# Clock_Distribution.net
KiCad netlist of a schematic drawn in Altium Designer
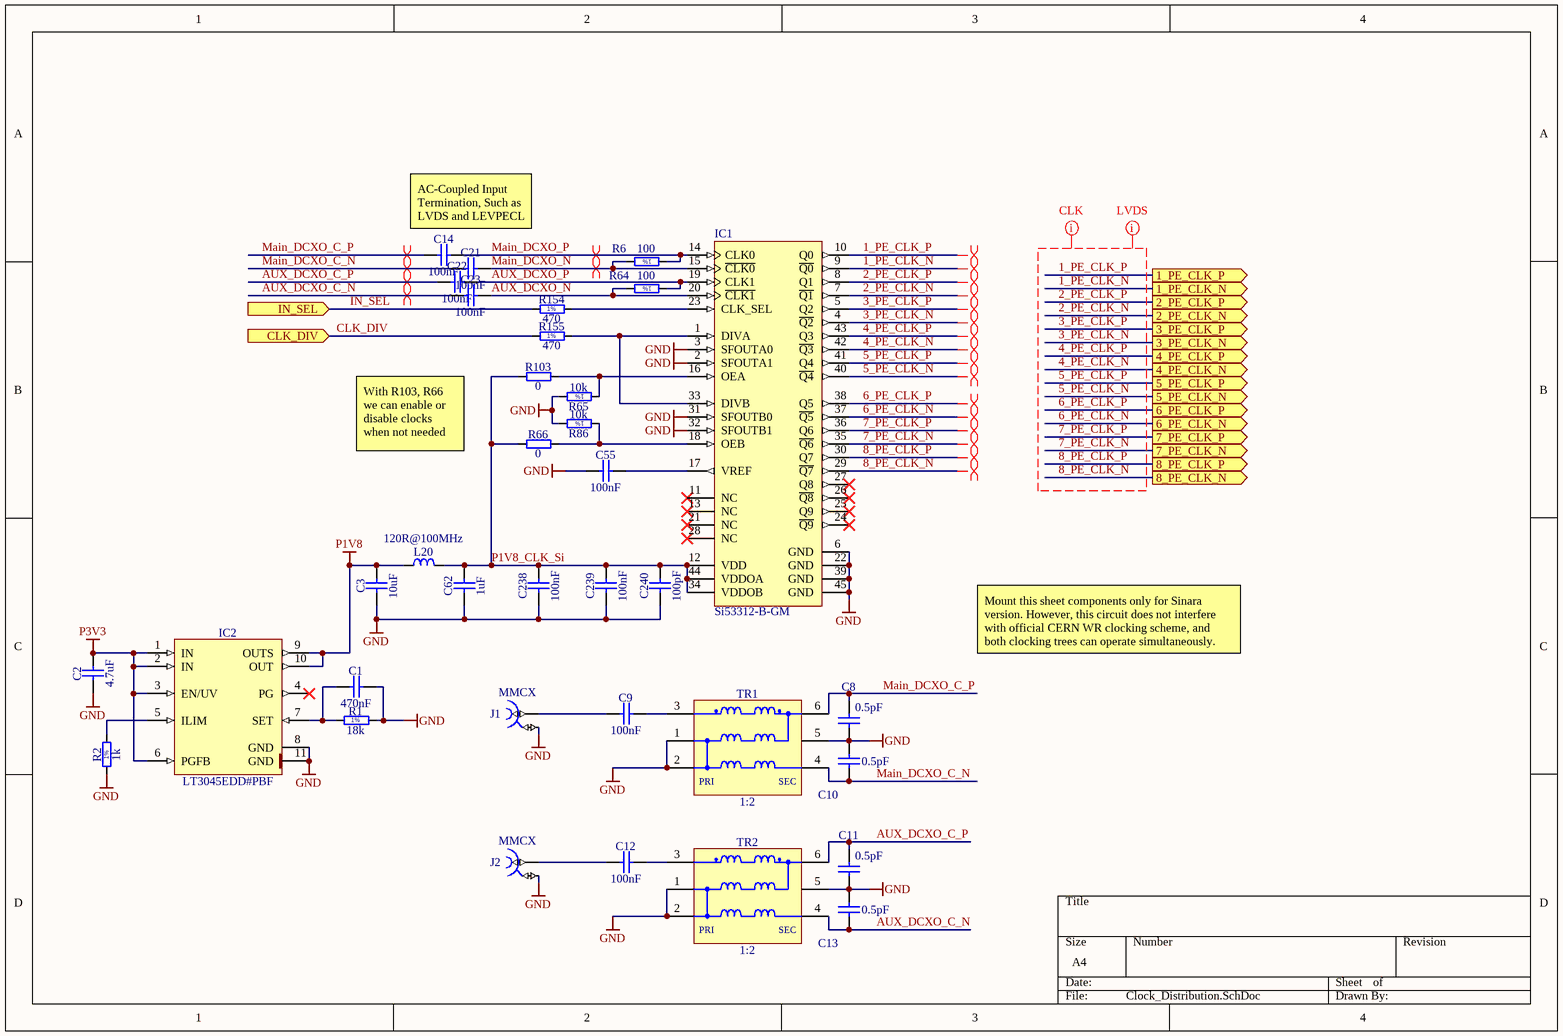
[diagram p0: Clock_Distribution.SchDoc]

(export (version "E")
  (design (tool "Eeschema 10.0.6"))
  (components
    (comp (ref "C1")
      (value "470nF")
      (footprint "CAPC1005X55N")
      (description "Non-polarised capacitor")
      (fields
        (field (name "PART NUMBER") "CC0402_470NF_16V_10%_X5R")
        (field (name "VOLTAGE") "16V")
        (field (name "AUTHOR") "CERN DEM JLC")
      )
      (libsource (lib "Capacitors") (part "Capacitor - non polarized"))
    )
    (comp (ref "C2")
      (value "4.7uF")
      (footprint "CAPC1709X95N")
      (description "Non-polarised capacitor")
      (fields
        (field (name "PART NUMBER") "CC0603_4.7UF_16V_10%_X5R")
        (field (name "VOLTAGE") "16V")
        (field (name "AUTHOR") "CERN DEM JLC")
      )
      (libsource (lib "Capacitors") (part "Capacitor - non polarized"))
    )
    (comp (ref "C3")
      (value "10uF")
      (footprint "CAPC1608X80N")
      (description "Non-polarised capacitor")
      (fields
        (field (name "PART NUMBER") "CC0603_10UF_10V_10%_X5R")
        (field (name "VOLTAGE") "10V")
        (field (name "AUTHOR") "CERN DEM JLC")
      )
      (libsource (lib "Capacitors") (part "Capacitor - non polarized"))
    )
    (comp (ref "C8")
      (value "0.5pF")
      (footprint "CAPC1005X50N")
      (description "Non-polarised capacitor")
      (fields
        (field (name "PART NUMBER") "CC0402_0.5PF_25V_0.05PF_AVX_04023J0R5ABSTR")
        (field (name "VOLTAGE") "25V")
        (field (name "AUTHOR") "CERN DEM JLC")
      )
      (libsource (lib "Capacitors") (part "Capacitor - non polarized"))
    )
    (comp (ref "C9")
      (value "100nF")
      (footprint "CAPC1005X55N")
      (description "Non-polarised capacitor")
      (fields
        (field (name "PART NUMBER") "CC0402_100NF_16V_10%_X5R")
        (field (name "VOLTAGE") "16V")
        (field (name "AUTHOR") "CERN DEM JLC")
      )
      (libsource (lib "Capacitors") (part "Capacitor - non polarized"))
    )
    (comp (ref "C10")
      (value "0.5pF")
      (footprint "CAPC1005X50N")
      (description "Non-polarised capacitor")
      (fields
        (field (name "PART NUMBER") "CC0402_0.5PF_25V_0.05PF_AVX_04023J0R5ABSTR")
        (field (name "VOLTAGE") "25V")
        (field (name "AUTHOR") "CERN DEM JLC")
      )
      (libsource (lib "Capacitors") (part "Capacitor - non polarized"))
    )
    (comp (ref "C11")
      (value "0.5pF")
      (footprint "CAPC1005X50N")
      (description "Non-polarised capacitor")
      (fields
        (field (name "PART NUMBER") "CC0402_0.5PF_25V_0.05PF_AVX_04023J0R5ABSTR")
        (field (name "VOLTAGE") "25V")
        (field (name "AUTHOR") "CERN DEM JLC")
      )
      (libsource (lib "Capacitors") (part "Capacitor - non polarized"))
    )
    (comp (ref "C12")
      (value "100nF")
      (footprint "CAPC1005X55N")
      (description "Non-polarised capacitor")
      (fields
        (field (name "PART NUMBER") "CC0402_100NF_16V_10%_X5R")
        (field (name "VOLTAGE") "16V")
        (field (name "AUTHOR") "CERN DEM JLC")
      )
      (libsource (lib "Capacitors") (part "Capacitor - non polarized"))
    )
    (comp (ref "C13")
      (value "0.5pF")
      (footprint "CAPC1005X50N")
      (description "Non-polarised capacitor")
      (fields
        (field (name "PART NUMBER") "CC0402_0.5PF_25V_0.05PF_AVX_04023J0R5ABSTR")
        (field (name "VOLTAGE") "25V")
        (field (name "AUTHOR") "CERN DEM JLC")
      )
      (libsource (lib "Capacitors") (part "Capacitor - non polarized"))
    )
    (comp (ref "C14")
      (value "100nF")
      (footprint "CAPC0603X33N")
      (description "Non-polarised capacitor")
      (fields
        (field (name "PART NUMBER") "CC0201_100NF_6.3V_10%_X5R")
        (field (name "VOLTAGE") "6.3V")
        (field (name "AUTHOR") "CERN DEM JLC")
      )
      (libsource (lib "Capacitors") (part "Capacitor - non polarized"))
    )
    (comp (ref "C21")
      (value "100nF")
      (footprint "CAPC0603X33N")
      (description "Non-polarised capacitor")
      (fields
        (field (name "PART NUMBER") "CC0201_100NF_6.3V_10%_X5R")
        (field (name "VOLTAGE") "6.3V")
        (field (name "AUTHOR") "CERN DEM JLC")
      )
      (libsource (lib "Capacitors") (part "Capacitor - non polarized"))
    )
    (comp (ref "C22")
      (value "100nF")
      (footprint "CAPC0603X33N")
      (description "Non-polarised capacitor")
      (fields
        (field (name "PART NUMBER") "CC0201_100NF_6.3V_10%_X5R")
        (field (name "VOLTAGE") "6.3V")
        (field (name "AUTHOR") "CERN DEM JLC")
      )
      (libsource (lib "Capacitors") (part "Capacitor - non polarized"))
    )
    (comp (ref "C23")
      (value "100nF")
      (footprint "CAPC0603X33N")
      (description "Non-polarised capacitor")
      (fields
        (field (name "PART NUMBER") "CC0201_100NF_6.3V_10%_X5R")
        (field (name "VOLTAGE") "6.3V")
        (field (name "AUTHOR") "CERN DEM JLC")
      )
      (libsource (lib "Capacitors") (part "Capacitor - non polarized"))
    )
    (comp (ref "C55")
      (value "100nF")
      (footprint "CAPC0603X33N")
      (description "Non-polarised capacitor")
      (fields
        (field (name "PART NUMBER") "CC0201_100NF_6.3V_10%_X5R")
        (field (name "VOLTAGE") "6.3V")
        (field (name "AUTHOR") "CERN DEM JLC")
      )
      (libsource (lib "Capacitors") (part "Capacitor - non polarized"))
    )
    (comp (ref "C62")
      (value "1uF")
      (footprint "CAPC1608X87N")
      (description "Non-polarised capacitor")
      (fields
        (field (name "PART NUMBER") "CC0603_1UF_25V_10%_X7R")
        (field (name "VOLTAGE") "25V")
        (field (name "AUTHOR") "CERN DEM JLC")
      )
      (libsource (lib "Capacitors") (part "Capacitor - non polarized"))
    )
    (comp (ref "C238")
      (value "100nF")
      (footprint "CAPC0603X33N")
      (description "Non-polarised capacitor")
      (fields
        (field (name "PART NUMBER") "CC0201_100NF_6.3V_10%_X5R")
        (field (name "VOLTAGE") "6.3V")
        (field (name "AUTHOR") "CERN DEM JLC")
      )
      (libsource (lib "Capacitors") (part "Capacitor - non polarized"))
    )
    (comp (ref "C239")
      (value "100nF")
      (footprint "CAPC0603X33N")
      (description "Non-polarised capacitor")
      (fields
        (field (name "PART NUMBER") "CC0201_100NF_6.3V_10%_X5R")
        (field (name "VOLTAGE") "6.3V")
        (field (name "AUTHOR") "CERN DEM JLC")
      )
      (libsource (lib "Capacitors") (part "Capacitor - non polarized"))
    )
    (comp (ref "C240")
      (value "100pF")
      (footprint "CAPC1005X55N")
      (description "Non-polarised capacitor")
      (fields
        (field (name "PART NUMBER") "CC0402_100PF_50V_5%_C0G")
        (field (name "VOLTAGE") "50V")
        (field (name "AUTHOR") "CERN DEM JLC")
      )
      (libsource (lib "Capacitors") (part "Capacitor - non polarized"))
    )
    (comp (ref "IC1")
      (value "Si53312-B-GM")
      (footprint "SLAB-QFN-44-2800x2800TP_N")
      (fields (field (name "MANUFACTURER") "Silicon Labs"))
      (libsource (lib "Altium Content Vault") (part "SLAB-Si53312-QFN-44-45"))
    )
    (comp (ref "IC2")
      (value "LT3045EDD#PBF")
      (footprint "SON50P300X300X80-11N-R175X248")
      (description "20V, 500mA, Ultralow Noise, Ultrahigh PSRR Linear Regulator")
      (fields (field (name "MANUFACTURER") "LINEAR TECHNOLOGY") (field (name "AUTHOR") "CERN DEM JLC"))
      (libsource (lib "ICs And Semiconductors") (part "LT3045EDD"))
    )
    (comp (ref "J1")
      (value "Coax_1Female_1Shield")
      (footprint "HUBER-SUHNER_85_MMCX-50-0-1/111_OE")
      (fields
        (field (name "PART NUMBER") "HUBER-SUHNER_85_MMCX-50-0-1/111_OE")
        (field (name "FAMILY") "MMCX")
        (field (name "MANUFACTURER") "HUBER+SUHNER")
        (field (name "MANUFACTURER PART NUMBER") "85_MMCX-50-0-1/111_OE")
        (field (name "AUTHOR") "CERN DEM JLC")
      )
      (libsource (lib "Connectors") (part "Coax_1Female_1Shield"))
    )
    (comp (ref "J2")
      (value "Coax_1Female_1Shield")
      (footprint "HUBER-SUHNER_85_MMCX-50-0-1/111_OE")
      (fields
        (field (name "PART NUMBER") "HUBER-SUHNER_85_MMCX-50-0-1/111_OE")
        (field (name "FAMILY") "MMCX")
        (field (name "MANUFACTURER") "HUBER+SUHNER")
        (field (name "MANUFACTURER PART NUMBER") "85_MMCX-50-0-1/111_OE")
        (field (name "AUTHOR") "CERN DEM JLC")
      )
      (libsource (lib "Connectors") (part "Coax_1Female_1Shield"))
    )
    (comp (ref "L20")
      (value "120R@100MHz")
      (footprint "INDC1608X95N")
      (description "Inductor")
      (fields
        (field (name "PART NUMBER") "IND0603_MURATA_BLM18PG121SN1D")
        (field (name "POWER") "2A")
        (field (name "AUTHOR") "CERN DEM BC")
      )
      (libsource (lib "Inductors & Transformers") (part "Inductor"))
    )
    (comp (ref "R1")
      (value "18k")
      (footprint "RESC1608X55N")
      (description "Resistor - 1%")
      (fields
        (field (name "PART NUMBER") "R0603_18K_1%_0.1W_100PPM")
        (field (name "POWER") "0.1W")
        (field (name "AUTHOR") "CERN DEM JLC")
      )
      (libsource (lib "Resistors") (part "Resistor - 1%"))
    )
    (comp (ref "R2")
      (value "1k")
      (footprint "RESC1005X40N")
      (description "Resistor - 1%")
      (fields
        (field (name "PART NUMBER") "R0402_1K_1%_0.0625W_100PPM")
        (field (name "POWER") "0.0625W")
        (field (name "AUTHOR") "CERN DEM JLC")
      )
      (libsource (lib "Resistors") (part "Resistor - 1%"))
    )
    (comp (ref "R6")
      (value "100")
      (footprint "RESC1005X40N")
      (description "Resistor - 1%")
      (fields
        (field (name "PART NUMBER") "R0402_100R_1%_0.0625W_100PPM")
        (field (name "POWER") "0.0625W")
        (field (name "AUTHOR") "CERN DEM JLC")
      )
      (libsource (lib "Resistors") (part "Resistor - 1%"))
    )
    (comp (ref "R64")
      (value "100")
      (footprint "RESC1005X40N")
      (description "Resistor - 1%")
      (fields
        (field (name "PART NUMBER") "R0402_100R_1%_0.0625W_100PPM")
        (field (name "POWER") "0.0625W")
        (field (name "AUTHOR") "CERN DEM JLC")
      )
      (libsource (lib "Resistors") (part "Resistor - 1%"))
    )
    (comp (ref "R65")
      (value "10k")
      (footprint "RESC1005X40N")
      (description "Resistor - 1%")
      (fields
        (field (name "PART NUMBER") "R0402_10K_1%_0.0625W_100PPM")
        (field (name "POWER") "0.0625W")
        (field (name "AUTHOR") "CERN DEM JLC")
      )
      (libsource (lib "Resistors") (part "Resistor - 1%"))
    )
    (comp (ref "R66")
      (value "0")
      (footprint "RESC1608X55N")
      (description "Resistor")
      (fields
        (field (name "PART NUMBER") "R0603_0R_JUMPER")
        (field (name "MANUFACTURER") "GENERIC")
        (field (name "AUTHOR") "CERN DEM JLC")
      )
      (libsource (lib "Resistors") (part "Resistor"))
    )
    (comp (ref "R86")
      (value "10k")
      (footprint "RESC1005X40N")
      (description "Resistor - 1%")
      (fields
        (field (name "PART NUMBER") "R0402_10K_1%_0.0625W_100PPM")
        (field (name "POWER") "0.0625W")
        (field (name "AUTHOR") "CERN DEM JLC")
      )
      (libsource (lib "Resistors") (part "Resistor - 1%"))
    )
    (comp (ref "R103")
      (value "0")
      (footprint "RESC1608X55N")
      (description "Resistor")
      (fields
        (field (name "PART NUMBER") "R0603_0R_JUMPER")
        (field (name "MANUFACTURER") "GENERIC")
        (field (name "AUTHOR") "CERN DEM JLC")
      )
      (libsource (lib "Resistors") (part "Resistor"))
    )
    (comp (ref "R154")
      (value "470")
      (footprint "RESC1005X40N")
      (description "Resistor - 1%")
      (fields
        (field (name "PART NUMBER") "R0402_470R_1%_0.0625W_100PPM")
        (field (name "POWER") "0.0625W")
        (field (name "AUTHOR") "CERN DEM JLC")
      )
      (libsource (lib "Resistors") (part "Resistor - 1%"))
    )
    (comp (ref "R155")
      (value "470")
      (footprint "RESC1005X40N")
      (description "Resistor - 1%")
      (fields
        (field (name "PART NUMBER") "R0402_470R_1%_0.0625W_100PPM")
        (field (name "POWER") "0.0625W")
        (field (name "AUTHOR") "CERN DEM JLC")
      )
      (libsource (lib "Resistors") (part "Resistor - 1%"))
    )
    (comp (ref "TR1")
      (value "1:2")
      (footprint "XFMR_MINI-CIRCUITS_DB1627")
      (description "50 OHMS 10 to 4000 MHz RF Transformer")
      (fields
        (field (name "PART NUMBER") "XFMR_MINI-CIRCUITS_TCM2-43X+")
        (field (name "POWER") "0.4W")
        (field (name "AUTHOR") "CERN DEM BC")
      )
      (libsource (lib "Inductors & Transformers") (part "XFMR_MINI-CIRCUITS_TCM2-43X"))
    )
    (comp (ref "TR2")
      (value "1:2")
      (footprint "XFMR_MINI-CIRCUITS_DB1627")
      (description "50 OHMS 10 to 4000 MHz RF Transformer")
      (fields
        (field (name "PART NUMBER") "XFMR_MINI-CIRCUITS_TCM2-43X+")
        (field (name "POWER") "0.4W")
        (field (name "AUTHOR") "CERN DEM BC")
      )
      (libsource (lib "Inductors & Transformers") (part "XFMR_MINI-CIRCUITS_TCM2-43X"))
    )
  )
  (nets
    (net (code "1") (name "/1_PE_CLK_N") (class "Default")
      (node (ref "IC1") (pin "9") (pinfunction "~{Q0}_9") (pintype "output"))
    )
    (net (code "2") (name "/1_PE_CLK_P") (class "Default")
      (node (ref "IC1") (pin "10") (pinfunction "Q0_10") (pintype "output"))
    )
    (net (code "3") (name "/2_PE_CLK_N") (class "Default")
      (node (ref "IC1") (pin "7") (pinfunction "~{Q1}_7") (pintype "output"))
    )
    (net (code "4") (name "/2_PE_CLK_P") (class "Default")
      (node (ref "IC1") (pin "8") (pinfunction "Q1_8") (pintype "output"))
    )
    (net (code "5") (name "/3_PE_CLK_N") (class "Default")
      (node (ref "IC1") (pin "4") (pinfunction "~{Q2}_4") (pintype "output"))
    )
    (net (code "6") (name "/3_PE_CLK_P") (class "Default")
      (node (ref "IC1") (pin "5") (pinfunction "Q2_5") (pintype "output"))
    )
    (net (code "7") (name "/4_PE_CLK_N") (class "Default")
      (node (ref "IC1") (pin "42") (pinfunction "~{Q3}_42") (pintype "output"))
    )
    (net (code "8") (name "/4_PE_CLK_P") (class "Default")
      (node (ref "IC1") (pin "43") (pinfunction "Q3_43") (pintype "output"))
    )
    (net (code "9") (name "/5_PE_CLK_N") (class "Default")
      (node (ref "IC1") (pin "40") (pinfunction "~{Q4}_40") (pintype "output"))
    )
    (net (code "10") (name "/5_PE_CLK_P") (class "Default")
      (node (ref "IC1") (pin "41") (pinfunction "Q4_41") (pintype "output"))
    )
    (net (code "11") (name "/6_PE_CLK_N") (class "Default")
      (node (ref "IC1") (pin "37") (pinfunction "~{Q5}_37") (pintype "output"))
    )
    (net (code "12") (name "/6_PE_CLK_P") (class "Default")
      (node (ref "IC1") (pin "38") (pinfunction "Q5_38") (pintype "output"))
    )
    (net (code "13") (name "/7_PE_CLK_N") (class "Default")
      (node (ref "IC1") (pin "35") (pinfunction "~{Q6}_35") (pintype "output"))
    )
    (net (code "14") (name "/7_PE_CLK_P") (class "Default")
      (node (ref "IC1") (pin "36") (pinfunction "Q6_36") (pintype "output"))
    )
    (net (code "15") (name "/8_PE_CLK_N") (class "Default")
      (node (ref "IC1") (pin "29") (pinfunction "~{Q7}_29") (pintype "output"))
    )
    (net (code "16") (name "/8_PE_CLK_P") (class "Default")
      (node (ref "IC1") (pin "30") (pinfunction "Q7_30") (pintype "output"))
    )
    (net (code "17") (name "/AUX_DCXO_C_N") (class "Default")
      (node (ref "C13") (pin "1") (pinfunction "1_1") (pintype "passive"))
      (node (ref "C23") (pin "1") (pinfunction "1_1") (pintype "passive"))
      (node (ref "TR2") (pin "4") (pinfunction "S1_4") (pintype "passive"))
    )
    (net (code "18") (name "/AUX_DCXO_C_P") (class "Default")
      (node (ref "C11") (pin "2") (pinfunction "2_2") (pintype "passive"))
      (node (ref "C22") (pin "1") (pinfunction "1_1") (pintype "passive"))
      (node (ref "TR2") (pin "6") (pinfunction "S1_6") (pintype "passive"))
    )
    (net (code "19") (name "/AUX_DCXO_N") (class "Default")
      (node (ref "C23") (pin "2") (pinfunction "2_2") (pintype "passive"))
      (node (ref "IC1") (pin "20") (pinfunction "~{CLK1}_20") (pintype "input"))
      (node (ref "R64") (pin "2") (pinfunction "2_2") (pintype "passive"))
    )
    (net (code "20") (name "/AUX_DCXO_P") (class "Default")
      (node (ref "C22") (pin "2") (pinfunction "2_2") (pintype "passive"))
      (node (ref "IC1") (pin "19") (pinfunction "CLK1_19") (pintype "input"))
      (node (ref "R64") (pin "1") (pinfunction "1_1") (pintype "passive"))
    )
    (net (code "21") (name "/CLK_DIV") (class "Default")
      (node (ref "R155") (pin "1") (pinfunction "1_1") (pintype "passive"))
    )
    (net (code "22") (name "/IN_SEL") (class "Default")
      (node (ref "R154") (pin "1") (pinfunction "1_1") (pintype "passive"))
    )
    (net (code "23") (name "/Main_DCXO_C_N") (class "Default")
      (node (ref "C10") (pin "1") (pinfunction "1_1") (pintype "passive"))
      (node (ref "C21") (pin "1") (pinfunction "1_1") (pintype "passive"))
      (node (ref "TR1") (pin "4") (pinfunction "S1_4") (pintype "passive"))
    )
    (net (code "24") (name "/Main_DCXO_C_P") (class "Default")
      (node (ref "C14") (pin "1") (pinfunction "1_1") (pintype "passive"))
      (node (ref "C8") (pin "2") (pinfunction "2_2") (pintype "passive"))
      (node (ref "TR1") (pin "6") (pinfunction "S1_6") (pintype "passive"))
    )
    (net (code "25") (name "/Main_DCXO_N") (class "Default")
      (node (ref "C21") (pin "2") (pinfunction "2_2") (pintype "passive"))
      (node (ref "IC1") (pin "15") (pinfunction "~{CLK0}_15") (pintype "input"))
      (node (ref "R6") (pin "2") (pinfunction "2_2") (pintype "passive"))
    )
    (net (code "26") (name "/Main_DCXO_P") (class "Default")
      (node (ref "C14") (pin "2") (pinfunction "2_2") (pintype "passive"))
      (node (ref "IC1") (pin "14") (pinfunction "CLK0_14") (pintype "input"))
      (node (ref "R6") (pin "1") (pinfunction "1_1") (pintype "passive"))
    )
    (net (code "27") (name "/P1V8_CLK_Si") (class "Default")
      (node (ref "C238") (pin "2") (pinfunction "2_2") (pintype "passive"))
      (node (ref "C239") (pin "2") (pinfunction "2_2") (pintype "passive"))
      (node (ref "C240") (pin "2") (pinfunction "2_2") (pintype "passive"))
      (node (ref "C62") (pin "2") (pinfunction "2_2") (pintype "passive"))
      (node (ref "IC1") (pin "12") (pinfunction "VDD_12") (pintype "power_in"))
      (node (ref "IC1") (pin "34") (pinfunction "VDDOB_34") (pintype "power_in"))
      (node (ref "IC1") (pin "44") (pinfunction "VDDOA_44") (pintype "power_in"))
      (node (ref "L20") (pin "1") (pinfunction "1_1") (pintype "passive"))
      (node (ref "R103") (pin "1") (pinfunction "1_1") (pintype "passive"))
      (node (ref "R66") (pin "1") (pinfunction "1_1") (pintype "passive"))
    )
    (net (code "28") (name "GND") (class "Default")
      (node (ref "C1") (pin "2") (pinfunction "2_2") (pintype "passive"))
      (node (ref "C10") (pin "2") (pinfunction "2_2") (pintype "passive"))
      (node (ref "C11") (pin "1") (pinfunction "1_1") (pintype "passive"))
      (node (ref "C13") (pin "2") (pinfunction "2_2") (pintype "passive"))
      (node (ref "C2") (pin "1") (pinfunction "1_1") (pintype "passive"))
      (node (ref "C238") (pin "1") (pinfunction "1_1") (pintype "passive"))
      (node (ref "C239") (pin "1") (pinfunction "1_1") (pintype "passive"))
      (node (ref "C240") (pin "1") (pinfunction "1_1") (pintype "passive"))
      (node (ref "C3") (pin "1") (pinfunction "1_1") (pintype "passive"))
      (node (ref "C55") (pin "1") (pinfunction "1_1") (pintype "passive"))
      (node (ref "C62") (pin "1") (pinfunction "1_1") (pintype "passive"))
      (node (ref "C8") (pin "1") (pinfunction "1_1") (pintype "passive"))
      (node (ref "IC1") (pin "2") (pinfunction "SFOUTA1_2") (pintype "input"))
      (node (ref "IC1") (pin "22") (pinfunction "GND_22") (pintype "power_in"))
      (node (ref "IC1") (pin "3") (pinfunction "SFOUTA0_3") (pintype "input"))
      (node (ref "IC1") (pin "31") (pinfunction "SFOUTB0_31") (pintype "input"))
      (node (ref "IC1") (pin "32") (pinfunction "SFOUTB1_32") (pintype "input"))
      (node (ref "IC1") (pin "39") (pinfunction "GND_39") (pintype "power_in"))
      (node (ref "IC1") (pin "45") (pinfunction "GND_45") (pintype "power_in"))
      (node (ref "IC1") (pin "6") (pinfunction "GND_6") (pintype "power_in"))
      (node (ref "IC2") (pin "11") (pinfunction "GND_11") (pintype "power_in"))
      (node (ref "IC2") (pin "8") (pinfunction "GND_8") (pintype "power_in"))
      (node (ref "J1") (pin "2") (pinfunction "2_2") (pintype "bidirectional"))
      (node (ref "J2") (pin "2") (pinfunction "2_2") (pintype "bidirectional"))
      (node (ref "R1") (pin "2") (pinfunction "2_2") (pintype "passive"))
      (node (ref "R2") (pin "1") (pinfunction "1_1") (pintype "passive"))
      (node (ref "R65") (pin "2") (pinfunction "2_2") (pintype "passive"))
      (node (ref "R86") (pin "2") (pinfunction "2_2") (pintype "passive"))
      (node (ref "TR1") (pin "1") (pinfunction "P1_1") (pintype "passive"))
      (node (ref "TR1") (pin "2") (pinfunction "P1_2") (pintype "passive"))
      (node (ref "TR1") (pin "5") (pinfunction "NC_5") (pintype "passive"))
      (node (ref "TR2") (pin "1") (pinfunction "P1_1") (pintype "passive"))
      (node (ref "TR2") (pin "2") (pinfunction "P1_2") (pintype "passive"))
      (node (ref "TR2") (pin "5") (pinfunction "NC_5") (pintype "passive"))
    )
    (net (code "29") (name "Net-(C9-Pad1)") (class "Default")
      (node (ref "C9") (pin "1") (pinfunction "1_1") (pintype "passive"))
      (node (ref "J1") (pin "1") (pinfunction "1_1") (pintype "bidirectional"))
    )
    (net (code "30") (name "Net-(C9-Pad2)") (class "Default")
      (node (ref "C9") (pin "2") (pinfunction "2_2") (pintype "passive"))
      (node (ref "TR1") (pin "3") (pinfunction "P1_3") (pintype "passive"))
    )
    (net (code "31") (name "Net-(C12-Pad1)") (class "Default")
      (node (ref "C12") (pin "1") (pinfunction "1_1") (pintype "passive"))
      (node (ref "J2") (pin "1") (pinfunction "1_1") (pintype "bidirectional"))
    )
    (net (code "32") (name "Net-(C12-Pad2)") (class "Default")
      (node (ref "C12") (pin "2") (pinfunction "2_2") (pintype "passive"))
      (node (ref "TR2") (pin "3") (pinfunction "P1_3") (pintype "passive"))
    )
    (net (code "33") (name "Net-(IC1-CLK_SEL)") (class "Default")
      (node (ref "IC1") (pin "23") (pinfunction "CLK_SEL_23") (pintype "input"))
      (node (ref "R154") (pin "2") (pinfunction "2_2") (pintype "passive"))
    )
    (net (code "34") (name "Net-(IC1-DIVA)") (class "Default")
      (node (ref "IC1") (pin "1") (pinfunction "DIVA_1") (pintype "input"))
      (node (ref "IC1") (pin "33") (pinfunction "DIVB_33") (pintype "input"))
      (node (ref "R155") (pin "2") (pinfunction "2_2") (pintype "passive"))
    )
    (net (code "35") (name "Net-(IC1-OEA)") (class "Default")
      (node (ref "IC1") (pin "16") (pinfunction "OEA_16") (pintype "input"))
      (node (ref "R103") (pin "2") (pinfunction "2_2") (pintype "passive"))
      (node (ref "R65") (pin "1") (pinfunction "1_1") (pintype "passive"))
    )
    (net (code "36") (name "Net-(IC1-OEB)") (class "Default")
      (node (ref "IC1") (pin "18") (pinfunction "OEB_18") (pintype "input"))
      (node (ref "R66") (pin "2") (pinfunction "2_2") (pintype "passive"))
      (node (ref "R86") (pin "1") (pinfunction "1_1") (pintype "passive"))
    )
    (net (code "37") (name "Net-(IC1-VREF)") (class "Default")
      (node (ref "C55") (pin "2") (pinfunction "2_2") (pintype "passive"))
      (node (ref "IC1") (pin "17") (pinfunction "VREF_17") (pintype "output"))
    )
    (net (code "38") (name "Net-(IC2-ILIM)") (class "Default")
      (node (ref "IC2") (pin "5") (pinfunction "ILIM_5") (pintype "input"))
      (node (ref "R2") (pin "2") (pinfunction "2_2") (pintype "passive"))
    )
    (net (code "39") (name "Net-(IC2-SET)") (class "Default")
      (node (ref "C1") (pin "1") (pinfunction "1_1") (pintype "passive"))
      (node (ref "IC2") (pin "7") (pinfunction "SET_7") (pintype "input"))
      (node (ref "R1") (pin "1") (pinfunction "1_1") (pintype "passive"))
    )
    (net (code "40") (name "P1V8") (class "Default")
      (node (ref "C3") (pin "2") (pinfunction "2_2") (pintype "passive"))
      (node (ref "IC2") (pin "10") (pinfunction "OUT_10") (pintype "output"))
      (node (ref "IC2") (pin "9") (pinfunction "OUTS_9") (pintype "output"))
      (node (ref "L20") (pin "2") (pinfunction "2_2") (pintype "passive"))
    )
    (net (code "41") (name "P3V3") (class "Default")
      (node (ref "C2") (pin "2") (pinfunction "2_2") (pintype "passive"))
      (node (ref "IC2") (pin "1") (pinfunction "IN_1") (pintype "input"))
      (node (ref "IC2") (pin "2") (pinfunction "IN_2") (pintype "input"))
      (node (ref "IC2") (pin "3") (pinfunction "EN/UV_3") (pintype "input"))
      (node (ref "IC2") (pin "6") (pinfunction "PGFB_6") (pintype "input"))
    )
    (net (code "42") (name "unconnected-(IC1-NC-Pad11)") (class "Default")
      (node (ref "IC1") (pin "11") (pinfunction "NC_11") (pintype "passive+no_connect"))
    )
    (net (code "43") (name "unconnected-(IC1-NC-Pad13)") (class "Default")
      (node (ref "IC1") (pin "13") (pinfunction "NC_13") (pintype "passive+no_connect"))
    )
    (net (code "44") (name "unconnected-(IC1-NC-Pad21)") (class "Default")
      (node (ref "IC1") (pin "21") (pinfunction "NC_21") (pintype "passive+no_connect"))
    )
    (net (code "45") (name "unconnected-(IC1-NC-Pad28)") (class "Default")
      (node (ref "IC1") (pin "28") (pinfunction "NC_28") (pintype "passive+no_connect"))
    )
    (net (code "46") (name "unconnected-(IC1-Q8-Pad27)") (class "Default")
      (node (ref "IC1") (pin "27") (pinfunction "Q8_27") (pintype "output+no_connect"))
    )
    (net (code "47") (name "unconnected-(IC1-Q9-Pad25)") (class "Default")
      (node (ref "IC1") (pin "25") (pinfunction "Q9_25") (pintype "output+no_connect"))
    )
    (net (code "48") (name "unconnected-(IC1-~{Q8}-Pad26)") (class "Default")
      (node (ref "IC1") (pin "26") (pinfunction "~{Q8}_26") (pintype "output+no_connect"))
    )
    (net (code "49") (name "unconnected-(IC1-~{Q9}-Pad24)") (class "Default")
      (node (ref "IC1") (pin "24") (pinfunction "~{Q9}_24") (pintype "output+no_connect"))
    )
    (net (code "50") (name "unconnected-(IC2-PG-Pad4)") (class "Default")
      (node (ref "IC2") (pin "4") (pinfunction "PG_4") (pintype "output+no_connect"))
    )
  )
)
